# musIR-tiny-mk-1_0_4.net
KiCad netlist of a schematic drawn in EAGLE
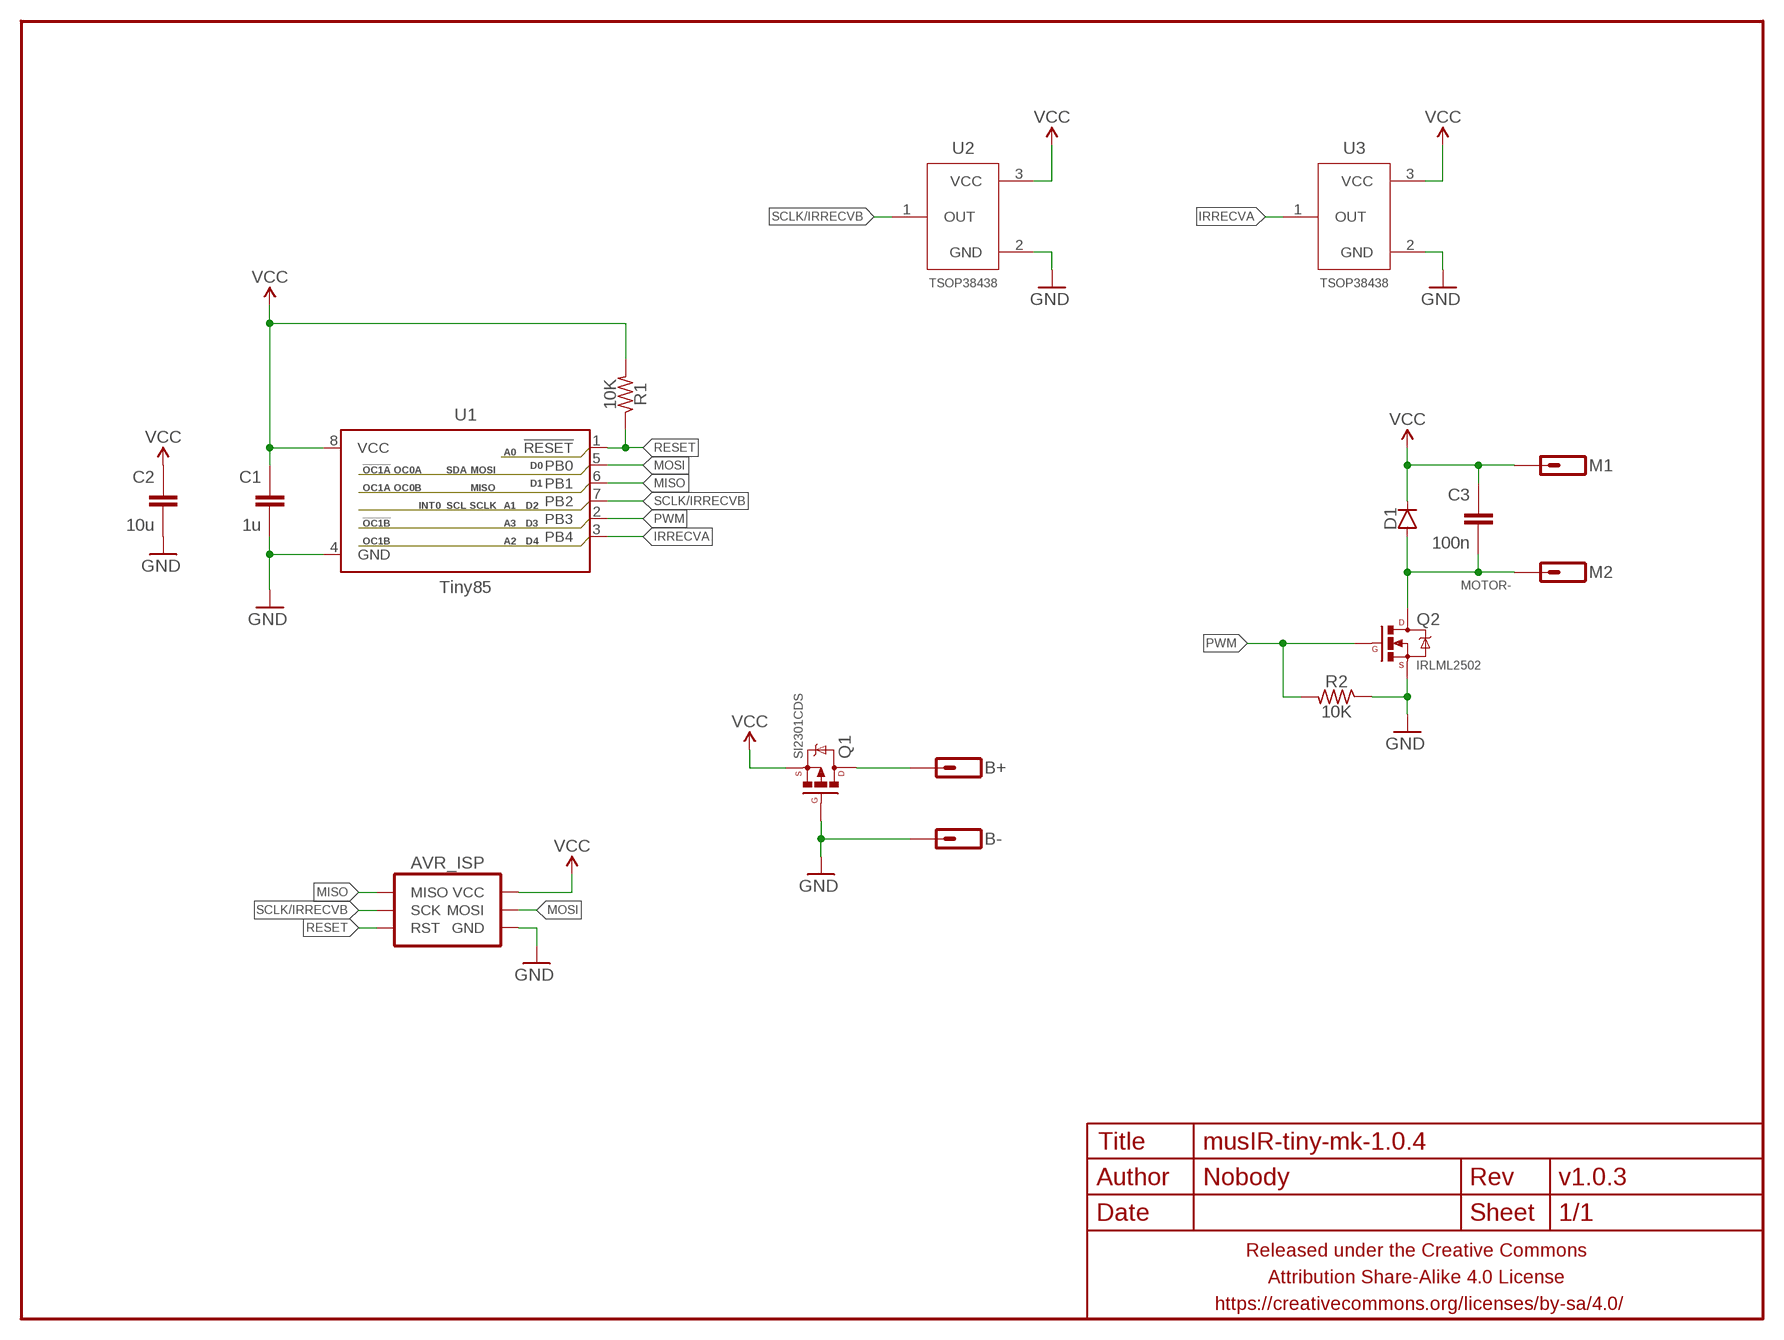
[diagram p0: schematic, sheet 1]

(export (version "E")
  (design (tool "Eeschema 10.0.6"))
  (components
    (comp (ref "AVR_ISP")
      (value "AVR_SPI_PRG_6TESTPOINTS")
      (footprint "eagle-import:2X3_TEST_POINTS")
      (libsource (lib "eagle-import") (part "AVR_SPI_PRG_6TESTPOINTS"))
    )
    (comp (ref "B+")
      (value "M01PTH")
      (footprint "eagle-import:1X01")
      (libsource (lib "eagle-import") (part "M01PTH"))
    )
    (comp (ref "B-")
      (value "M01PTH")
      (footprint "eagle-import:1X01")
      (libsource (lib "eagle-import") (part "M01PTH"))
    )
    (comp (ref "C1")
      (value "1u")
      (footprint "eagle-import:C0603-TIGHTER")
      (libsource (lib "eagle-import") (part "CAPACITOR-CERAMICC0603-TIGHTER"))
    )
    (comp (ref "C2")
      (value "10u")
      (footprint "eagle-import:C0805-TIGHTER")
      (libsource (lib "eagle-import") (part "CAPACITOR-CERAMICC0805-TIGHTER"))
    )
    (comp (ref "C3")
      (value "100n")
      (footprint "eagle-import:C0603-TIGHTER")
      (libsource (lib "eagle-import") (part "CAPACITOR-CERAMICC0603-TIGHTER"))
    )
    (comp (ref "D1")
      (value "DIODESOD123")
      (footprint "eagle-import:SOD123")
      (libsource (lib "eagle-import") (part "DIODESOD123"))
    )
    (comp (ref "FRAME1")
      (value "FRAME-LETTERNO_PACKAGE")
      (footprint "eagle-import:DUMMY")
      (fields (field (name "VERSION") "v1.0.3") (field (name "DESIGNER") "Nobody"))
      (libsource (lib "eagle-import") (part "FRAME-LETTERNO_PACKAGE"))
    )
    (comp (ref "M1")
      (value "M01PTH")
      (footprint "eagle-import:1X01")
      (libsource (lib "eagle-import") (part "M01PTH"))
    )
    (comp (ref "M2")
      (value "M01PTH")
      (footprint "eagle-import:1X01")
      (libsource (lib "eagle-import") (part "M01PTH"))
    )
    (comp (ref "Q1")
      (value "SI2301CDS")
      (footprint "eagle-import:SOT23")
      (libsource (lib "eagle-import") (part "MOSFET-PCHANNELSOT-23"))
    )
    (comp (ref "Q2")
      (value "IRLML2502")
      (footprint "eagle-import:SOT23")
      (libsource (lib "eagle-import") (part "MOSFET-NCHANNELIRLML2502"))
    )
    (comp (ref "R1")
      (value "10K")
      (footprint "eagle-import:R0603-TIGHTER")
      (libsource (lib "eagle-import") (part "RESISTORR0603-TIGHTER"))
    )
    (comp (ref "R2")
      (value "10K")
      (footprint "eagle-import:R0603-TIGHTER")
      (libsource (lib "eagle-import") (part "RESISTORR0603-TIGHTER"))
    )
    (comp (ref "U1")
      (value "Tiny85")
      (footprint "eagle-import:SO08-EIAJ")
      (libsource (lib "eagle-import") (part "ATTINY45TINY85-20-SOICW"))
    )
    (comp (ref "U2")
      (value "TSOP38438")
      (footprint "eagle-import:TSOP38238")
      (libsource (lib "eagle-import") (part "TSOP382__/4__"))
    )
    (comp (ref "U3")
      (value "TSOP38438")
      (footprint "eagle-import:TSOP38238")
      (libsource (lib "eagle-import") (part "TSOP382__/4__"))
    )
  )
  (nets
    (net (code "1") (name "/MOTOR-") (class "Default")
      (node (ref "C3") (pin "2") (pinfunction "2_2") (pintype "passive"))
      (node (ref "D1") (pin "A") (pinfunction "A_A") (pintype "passive"))
      (node (ref "M2") (pin "1") (pinfunction "1_1") (pintype "passive"))
      (node (ref "Q2") (pin "3") (pinfunction "D_3") (pintype "passive"))
    )
    (net (code "2") (name "GND") (class "Default")
      (node (ref "AVR_ISP") (pin "6") (pinfunction "GND_6") (pintype "passive"))
      (node (ref "B-") (pin "1") (pinfunction "1_1") (pintype "passive"))
      (node (ref "C1") (pin "2") (pinfunction "2_2") (pintype "passive"))
      (node (ref "C2") (pin "2") (pinfunction "2_2") (pintype "passive"))
      (node (ref "Q1") (pin "1") (pinfunction "G_1") (pintype "passive"))
      (node (ref "Q2") (pin "2") (pinfunction "S_2") (pintype "passive"))
      (node (ref "R2") (pin "1") (pinfunction "1_1") (pintype "passive"))
      (node (ref "U1") (pin "4") (pinfunction "GND_4") (pintype "bidirectional"))
      (node (ref "U2") (pin "2") (pinfunction "GND_2") (pintype "bidirectional"))
      (node (ref "U3") (pin "2") (pinfunction "GND_2") (pintype "bidirectional"))
    )
    (net (code "3") (name "IRRECVA") (class "Default")
      (node (ref "U1") (pin "3") (pinfunction "PB4_3") (pintype "bidirectional"))
      (node (ref "U3") (pin "1") (pinfunction "OUT_1") (pintype "bidirectional"))
    )
    (net (code "4") (name "MISO") (class "Default")
      (node (ref "AVR_ISP") (pin "1") (pinfunction "MISO_1") (pintype "passive"))
      (node (ref "U1") (pin "6") (pinfunction "PB1_6") (pintype "bidirectional"))
    )
    (net (code "5") (name "MOSI") (class "Default")
      (node (ref "AVR_ISP") (pin "4") (pinfunction "MOSI_4") (pintype "passive"))
      (node (ref "U1") (pin "5") (pinfunction "PB0_5") (pintype "bidirectional"))
    )
    (net (code "6") (name "Net-(Q1-D)") (class "Default")
      (node (ref "B+") (pin "1") (pinfunction "1_1") (pintype "passive"))
      (node (ref "Q1") (pin "3") (pinfunction "D_3") (pintype "passive"))
    )
    (net (code "7") (name "PWM") (class "Default")
      (node (ref "Q2") (pin "1") (pinfunction "G_1") (pintype "passive"))
      (node (ref "R2") (pin "2") (pinfunction "2_2") (pintype "passive"))
      (node (ref "U1") (pin "2") (pinfunction "PB3_2") (pintype "bidirectional"))
    )
    (net (code "8") (name "RESET") (class "Default")
      (node (ref "AVR_ISP") (pin "5") (pinfunction "RST_5") (pintype "passive"))
      (node (ref "R1") (pin "1") (pinfunction "1_1") (pintype "passive"))
      (node (ref "U1") (pin "1") (pinfunction "~{RESET}_1") (pintype "bidirectional"))
    )
    (net (code "9") (name "SCLK{slash}IRRECVB") (class "Default")
      (node (ref "AVR_ISP") (pin "3") (pinfunction "SCK_3") (pintype "passive"))
      (node (ref "U1") (pin "7") (pinfunction "PB2_7") (pintype "bidirectional"))
      (node (ref "U2") (pin "1") (pinfunction "OUT_1") (pintype "bidirectional"))
    )
    (net (code "10") (name "VCC") (class "Default")
      (node (ref "AVR_ISP") (pin "2") (pinfunction "VCC_2") (pintype "passive"))
      (node (ref "C1") (pin "1") (pinfunction "1_1") (pintype "passive"))
      (node (ref "C2") (pin "1") (pinfunction "1_1") (pintype "passive"))
      (node (ref "C3") (pin "1") (pinfunction "1_1") (pintype "passive"))
      (node (ref "D1") (pin "C") (pinfunction "C_C") (pintype "passive"))
      (node (ref "M1") (pin "1") (pinfunction "1_1") (pintype "passive"))
      (node (ref "Q1") (pin "2") (pinfunction "S_2") (pintype "passive"))
      (node (ref "R1") (pin "2") (pinfunction "2_2") (pintype "passive"))
      (node (ref "U1") (pin "8") (pinfunction "VCC_8") (pintype "bidirectional"))
      (node (ref "U2") (pin "3") (pinfunction "VCC_3") (pintype "bidirectional"))
      (node (ref "U3") (pin "3") (pinfunction "VCC_3") (pintype "bidirectional"))
    )
  )
)
